# Sheet_1_2024-05-18.net
KiCad netlist of a schematic drawn in Altium Designer
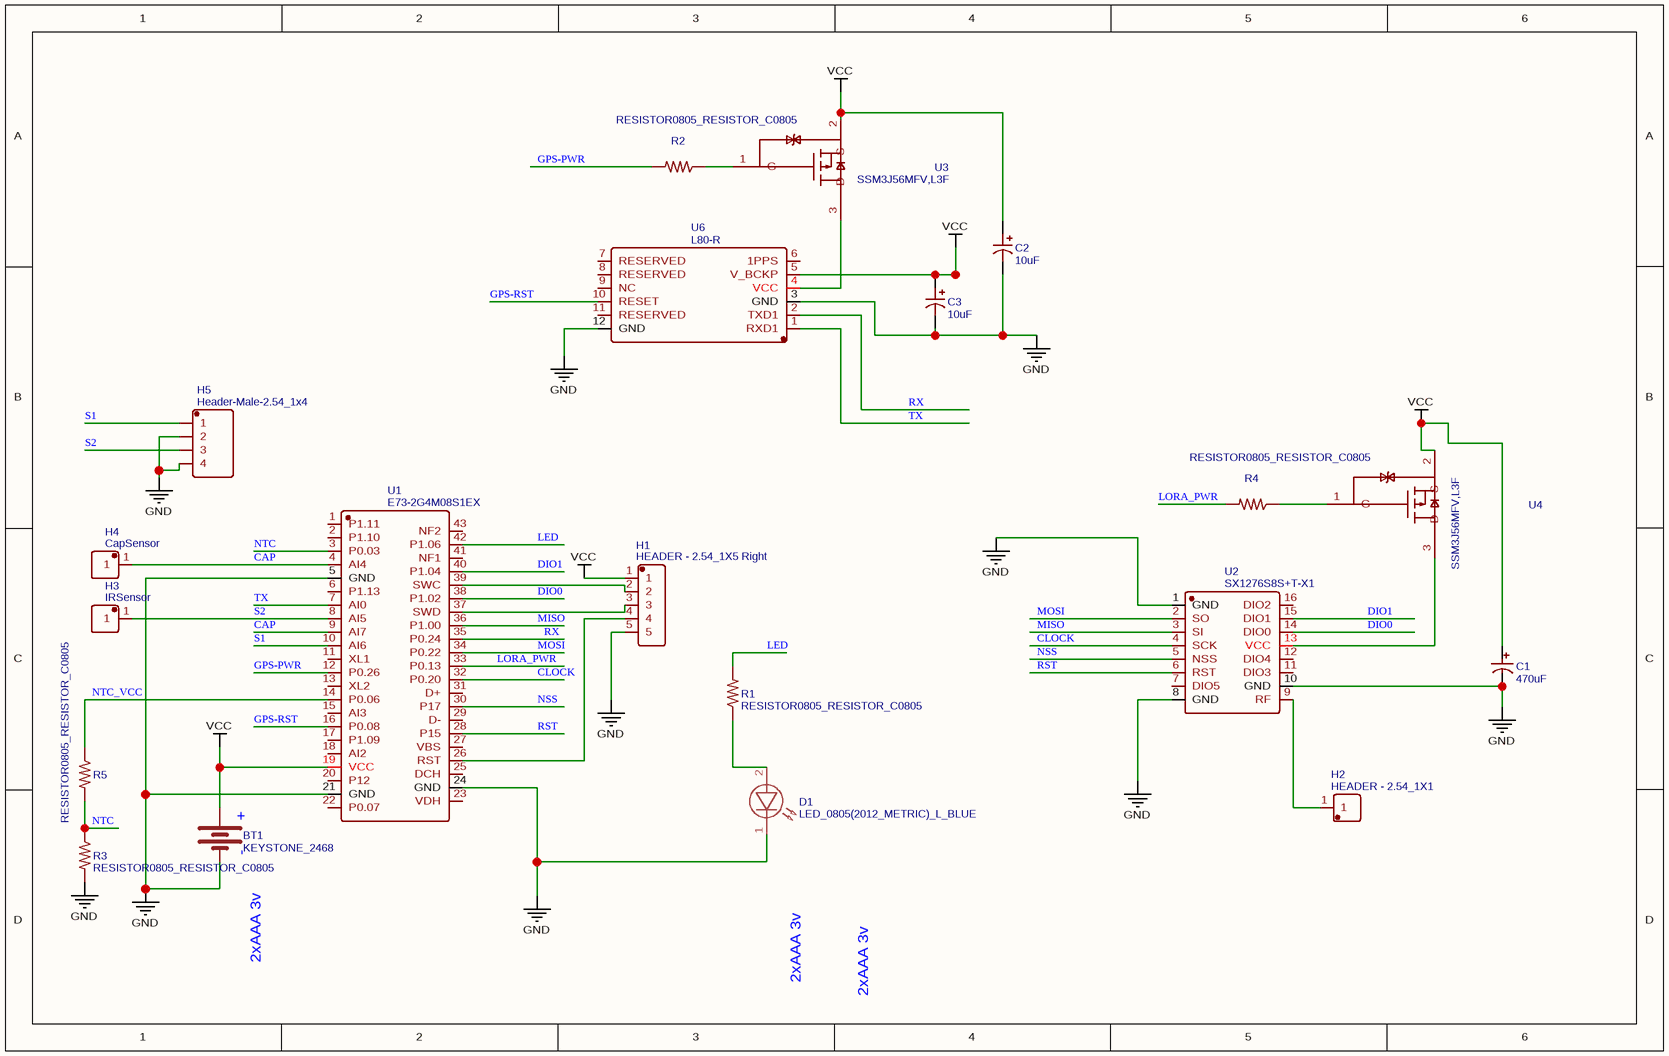
[diagram p0: Sheet_1_2024-05-18.schdoc]

(export (version "E")
  (design (tool "Eeschema 10.0.6"))
  (components
    (comp (ref "BT1")
      (value "KEYSTONE_2468")
      (fields
        (field (name "MANUFACTURER") "Keystone")
        (field (name "MANUFACTURER PART") "2468")
        (field (name "CONTRIBUTOR") "a.karnauh")
      )
      (libsource (lib "altium-import") (part "root_3_KEYSTONE_2468_"))
    )
    (comp (ref "C1")
      (value "470uF")
      (fields
        (field (name "MANUFACTURER") "ValuePro")
        (field (name "MANUFACTURER PART") "470uF 10V白纸 13*25")
        (field (name "CONTRIBUTOR") "baongoc1234abcd")
      )
      (libsource (lib "altium-import") (part "root_3_470uF_"))
    )
    (comp (ref "C2")
      (value "10uF")
      (fields
        (field (name "MANUFACTURER") "CEC(振华新云)")
        (field (name "MANUFACTURER PART") "CA45-B-10V-10UF-K")
        (field (name "CONTRIBUTOR") "lcsc")
      )
      (libsource (lib "altium-import") (part "root_3_10uF_"))
    )
    (comp (ref "C3")
      (value "10uF")
      (fields
        (field (name "MANUFACTURER") "CEC(振华新云)")
        (field (name "MANUFACTURER PART") "CA45-B-10V-10UF-K")
        (field (name "CONTRIBUTOR") "lcsc")
      )
      (libsource (lib "altium-import") (part "root_3_10uF_"))
    )
    (comp (ref "D1")
      (value "LED_0805(2012_METRIC)_L_BLUE")
      (fields (field (name "CONTRIBUTOR") "Ілля Бондаренко"))
      (libsource (lib "altium-import") (part "root_3_LED_0805(2012_METRIC)_L_BLUE_"))
    )
    (comp (ref "H1")
      (value "HEADER - 2.54_1X5 Right")
      (fields (field (name "CONTRIBUTOR") "Jonathan Gainsford"))
      (libsource (lib "altium-import") (part "root_0_HEADER - 2.54_1X5 Right_"))
    )
    (comp (ref "H2")
      (value "HEADER - 2.54_1X1")
      (fields (field (name "CONTRIBUTOR") "ASP-29 Tech"))
      (libsource (lib "altium-import") (part "root_0_HEADER - 2.54_1X1_"))
    )
    (comp (ref "H3")
      (value "IRSensor")
      (fields (field (name "CONTRIBUTOR") "ASP-29 Tech"))
      (libsource (lib "altium-import") (part "root_2_IRSensor_"))
    )
    (comp (ref "H4")
      (value "CapSensor")
      (fields (field (name "CONTRIBUTOR") "ASP-29 Tech"))
      (libsource (lib "altium-import") (part "root_2_CapSensor_"))
    )
    (comp (ref "H5")
      (value "Header-Male-2.54_1x4")
      (fields
        (field (name "MANUFACTURER") "Ckmtw(灿科盟)")
        (field (name "MANUFACTURER PART") "B-2100S04P-A110")
        (field (name "CONTRIBUTOR") "LCSC")
      )
      (libsource (lib "altium-import") (part "root_0_Header-Male-2.54_1x4_"))
    )
    (comp (ref "R1")
      (value "RESISTOR0805_RESISTOR_C0805")
      (fields (field (name "MANUFACTURER") "2.2K"))
      (libsource (lib "altium-import") (part "root_1_RESISTOR0805_RESISTOR_C0805_"))
    )
    (comp (ref "R2")
      (value "RESISTOR0805_RESISTOR_C0805")
      (fields (field (name "MANUFACTURER") "10K"))
      (libsource (lib "altium-import") (part "root_2_RESISTOR0805_RESISTOR_C0805_"))
    )
    (comp (ref "R3")
      (value "RESISTOR0805_RESISTOR_C0805")
      (fields (field (name "MANUFACTURER") "NTC 10K"))
      (libsource (lib "altium-import") (part "root_3_RESISTOR0805_RESISTOR_C0805_"))
    )
    (comp (ref "R4")
      (value "RESISTOR0805_RESISTOR_C0805")
      (fields (field (name "MANUFACTURER") "10K"))
      (libsource (lib "altium-import") (part "root_2_RESISTOR0805_RESISTOR_C0805_"))
    )
    (comp (ref "R5")
      (value "RESISTOR0805_RESISTOR_C0805")
      (fields (field (name "MANUFACTURER") "10K"))
      (libsource (lib "altium-import") (part "root_3_RESISTOR0805_RESISTOR_C0805_"))
    )
    (comp (ref "U1")
      (value "E73-2G4M08S1EX")
      (fields (field (name "MANUFACTURER") "EBYTE(亿佰特)") (field (name "CONTRIBUTOR") "lcsc"))
      (libsource (lib "altium-import") (part "root_0_E73-2G4M08S1EX_"))
    )
    (comp (ref "U2")
      (value "SX1276S8S+T-X1")
      (fields (field (name "MANUFACTURER") "Vollgo(沃进)") (field (name "CONTRIBUTOR") "LCSC"))
      (libsource (lib "altium-import") (part "root_0_SX1276S8S+T-X1_"))
    )
    (comp (ref "U3")
      (value "SSM3J56MFV,L3F")
      (fields (field (name "MANUFACTURER") "TOSHIBA(东芝)") (field (name "CONTRIBUTOR") "lcsc"))
      (libsource (lib "altium-import") (part "root_2_SSM3J56MFV,L3F_"))
    )
    (comp (ref "U4")
      (value "SSM3J56MFV,L3F")
      (fields (field (name "MANUFACTURER") "TOSHIBA(东芝)") (field (name "CONTRIBUTOR") "lcsc"))
      (libsource (lib "altium-import") (part "root_2_SSM3J56MFV,L3F_"))
    )
    (comp (ref "U6")
      (value "L80-R")
      (fields (field (name "MANUFACTURER") "Quectel(移远)") (field (name "CONTRIBUTOR") "LCSC"))
      (libsource (lib "altium-import") (part "root_0_L80-R_"))
    )
  )
  (nets
    (net (code "1") (name "/CAP") (class "Default")
      (node (ref "H4") (pin "1") (pinfunction "1_1") (pintype "passive"))
      (node (ref "U1") (pin "4") (pinfunction "AI4_4") (pintype "passive"))
      (node (ref "U1") (pin "9") (pinfunction "AI7_9") (pintype "passive"))
    )
    (net (code "2") (name "/CLOCK") (class "Default")
      (node (ref "U1") (pin "32") (pinfunction "P0.20_32") (pintype "passive"))
      (node (ref "U2") (pin "4") (pinfunction "SCK_4") (pintype "passive"))
    )
    (net (code "3") (name "/DIO0") (class "Default")
      (node (ref "U1") (pin "38") (pinfunction "P1.02_38") (pintype "passive"))
      (node (ref "U2") (pin "14") (pinfunction "DIO0_14") (pintype "passive"))
    )
    (net (code "4") (name "/DIO1") (class "Default")
      (node (ref "U1") (pin "40") (pinfunction "P1.04_40") (pintype "passive"))
      (node (ref "U2") (pin "15") (pinfunction "DIO1_15") (pintype "passive"))
    )
    (net (code "5") (name "/GPS-PWR") (class "Default")
      (node (ref "R2") (pin "2") (pinfunction "2_2") (pintype "passive"))
      (node (ref "U1") (pin "12") (pinfunction "P0.26_12") (pintype "passive"))
    )
    (net (code "6") (name "/GPS-RST") (class "Default")
      (node (ref "U1") (pin "16") (pinfunction "P0.08_16") (pintype "passive"))
      (node (ref "U6") (pin "10") (pinfunction "RESET_10") (pintype "passive"))
    )
    (net (code "7") (name "/LED") (class "Default")
      (node (ref "R1") (pin "2") (pinfunction "2_2") (pintype "passive"))
      (node (ref "U1") (pin "42") (pinfunction "P1.06_42") (pintype "passive"))
    )
    (net (code "8") (name "/LORA_PWR") (class "Default")
      (node (ref "R4") (pin "2") (pinfunction "2_2") (pintype "passive"))
      (node (ref "U1") (pin "33") (pinfunction "P0.13_33") (pintype "passive"))
    )
    (net (code "9") (name "/MISO") (class "Default")
      (node (ref "U1") (pin "36") (pinfunction "P1.00_36") (pintype "passive"))
      (node (ref "U2") (pin "3") (pinfunction "SI_3") (pintype "passive"))
    )
    (net (code "10") (name "/MOSI") (class "Default")
      (node (ref "U1") (pin "34") (pinfunction "P0.22_34") (pintype "passive"))
      (node (ref "U2") (pin "2") (pinfunction "SO_2") (pintype "passive"))
    )
    (net (code "11") (name "/NSS") (class "Default")
      (node (ref "U1") (pin "30") (pinfunction "P17_30") (pintype "passive"))
      (node (ref "U2") (pin "5") (pinfunction "NSS_5") (pintype "passive"))
    )
    (net (code "12") (name "/NTC") (class "Default")
      (node (ref "R3") (pin "1") (pinfunction "1_1") (pintype "passive"))
      (node (ref "R5") (pin "2") (pinfunction "2_2") (pintype "passive"))
      (node (ref "U1") (pin "3") (pinfunction "P0.03_3") (pintype "passive"))
    )
    (net (code "13") (name "/NTC_VCC") (class "Default")
      (node (ref "R5") (pin "1") (pinfunction "1_1") (pintype "passive"))
      (node (ref "U1") (pin "14") (pinfunction "P0.06_14") (pintype "passive"))
    )
    (net (code "14") (name "/RST") (class "Default")
      (node (ref "U1") (pin "28") (pinfunction "P15_28") (pintype "passive"))
      (node (ref "U2") (pin "6") (pinfunction "RST_6") (pintype "passive"))
    )
    (net (code "15") (name "/RX") (class "Default")
      (node (ref "U1") (pin "35") (pinfunction "P0.24_35") (pintype "passive"))
      (node (ref "U6") (pin "2") (pinfunction "TXD1_2") (pintype "passive"))
    )
    (net (code "16") (name "/S1") (class "Default")
      (node (ref "H5") (pin "1") (pinfunction "1_1") (pintype "passive"))
      (node (ref "U1") (pin "10") (pinfunction "AI6_10") (pintype "passive"))
    )
    (net (code "17") (name "/S2") (class "Default")
      (node (ref "H3") (pin "1") (pinfunction "1_1") (pintype "passive"))
      (node (ref "H5") (pin "3") (pinfunction "3_3") (pintype "passive"))
      (node (ref "U1") (pin "8") (pinfunction "AI5_8") (pintype "passive"))
    )
    (net (code "18") (name "/TX") (class "Default")
      (node (ref "U1") (pin "7") (pinfunction "AI0_7") (pintype "passive"))
      (node (ref "U6") (pin "1") (pinfunction "RXD1_1") (pintype "passive"))
    )
    (net (code "19") (name "GND") (class "Default")
      (node (ref "BT1") (pin "2") (pinfunction "-_2") (pintype "passive"))
      (node (ref "C1") (pin "2") (pinfunction "2_2") (pintype "passive"))
      (node (ref "C2") (pin "2") (pinfunction "2_2") (pintype "passive"))
      (node (ref "C3") (pin "2") (pinfunction "2_2") (pintype "passive"))
      (node (ref "D1") (pin "1") (pinfunction "K_1") (pintype "passive"))
      (node (ref "H1") (pin "5") (pinfunction "5_5") (pintype "passive"))
      (node (ref "H5") (pin "2") (pinfunction "2_2") (pintype "passive"))
      (node (ref "H5") (pin "4") (pinfunction "4_4") (pintype "passive"))
      (node (ref "R3") (pin "2") (pinfunction "2_2") (pintype "passive"))
      (node (ref "U1") (pin "21") (pinfunction "GND_21") (pintype "passive"))
      (node (ref "U1") (pin "24") (pinfunction "GND_24") (pintype "passive"))
      (node (ref "U1") (pin "5") (pinfunction "GND_5") (pintype "passive"))
      (node (ref "U2") (pin "1") (pinfunction "GND_1") (pintype "passive"))
      (node (ref "U2") (pin "10") (pinfunction "GND_10") (pintype "passive"))
      (node (ref "U2") (pin "8") (pinfunction "GND_8") (pintype "passive"))
      (node (ref "U6") (pin "12") (pinfunction "GND_12") (pintype "passive"))
      (node (ref "U6") (pin "3") (pinfunction "GND_3") (pintype "passive"))
    )
    (net (code "20") (name "Net-(D1-A)") (class "Default")
      (node (ref "D1") (pin "2") (pinfunction "A_2") (pintype "passive"))
      (node (ref "R1") (pin "1") (pinfunction "1_1") (pintype "passive"))
    )
    (net (code "21") (name "Net-(U1-RST)") (class "Default")
      (node (ref "H1") (pin "4") (pinfunction "4_4") (pintype "passive"))
      (node (ref "U1") (pin "26") (pinfunction "RST_26") (pintype "passive"))
    )
    (net (code "22") (name "Net-(U1-SWC)") (class "Default")
      (node (ref "H1") (pin "2") (pinfunction "2_2") (pintype "passive"))
      (node (ref "U1") (pin "39") (pinfunction "SWC_39") (pintype "passive"))
    )
    (net (code "23") (name "Net-(U1-SWD)") (class "Default")
      (node (ref "H1") (pin "3") (pinfunction "3_3") (pintype "passive"))
      (node (ref "U1") (pin "37") (pinfunction "SWD_37") (pintype "passive"))
    )
    (net (code "24") (name "Net-(U2-RF)") (class "Default")
      (node (ref "H2") (pin "1") (pinfunction "1_1") (pintype "passive"))
      (node (ref "U2") (pin "9") (pinfunction "RF_9") (pintype "passive"))
    )
    (net (code "25") (name "Net-(U2-VCC)") (class "Default")
      (node (ref "U2") (pin "13") (pinfunction "VCC_13") (pintype "passive"))
      (node (ref "U4") (pin "3") (pinfunction "D_3") (pintype "passive"))
    )
    (net (code "26") (name "Net-(U3-D)") (class "Default")
      (node (ref "U3") (pin "3") (pinfunction "D_3") (pintype "passive"))
      (node (ref "U6") (pin "4") (pinfunction "VCC_4") (pintype "passive"))
    )
    (net (code "27") (name "Net-(U3-G)") (class "Default")
      (node (ref "R2") (pin "1") (pinfunction "1_1") (pintype "passive"))
      (node (ref "U3") (pin "1") (pinfunction "G_1") (pintype "passive"))
    )
    (net (code "28") (name "Net-(U4-G)") (class "Default")
      (node (ref "R4") (pin "1") (pinfunction "1_1") (pintype "passive"))
      (node (ref "U4") (pin "1") (pinfunction "G_1") (pintype "passive"))
    )
    (net (code "29") (name "VCC") (class "Default")
      (node (ref "BT1") (pin "1") (pinfunction "+_1") (pintype "passive"))
      (node (ref "C1") (pin "1") (pinfunction "1_1") (pintype "passive"))
      (node (ref "C2") (pin "1") (pinfunction "1_1") (pintype "passive"))
      (node (ref "C3") (pin "1") (pinfunction "1_1") (pintype "passive"))
      (node (ref "H1") (pin "1") (pinfunction "1_1") (pintype "passive"))
      (node (ref "U1") (pin "19") (pinfunction "VCC_19") (pintype "passive"))
      (node (ref "U3") (pin "2") (pinfunction "S_2") (pintype "passive"))
      (node (ref "U4") (pin "2") (pinfunction "S_2") (pintype "passive"))
      (node (ref "U6") (pin "5") (pinfunction "V_BCKP_5") (pintype "passive"))
    )
    (net (code "30") (name "unconnected-(U1-AI2-Pad18)") (class "Default")
      (node (ref "U1") (pin "18") (pinfunction "AI2_18") (pintype "passive"))
    )
    (net (code "31") (name "unconnected-(U1-AI3-Pad15)") (class "Default")
      (node (ref "U1") (pin "15") (pinfunction "AI3_15") (pintype "passive"))
    )
    (net (code "32") (name "unconnected-(U1-D+-Pad31)") (class "Default")
      (node (ref "U1") (pin "31") (pinfunction "D+_31") (pintype "passive"))
    )
    (net (code "33") (name "unconnected-(U1-D--Pad29)") (class "Default")
      (node (ref "U1") (pin "29") (pinfunction "D-_29") (pintype "passive"))
    )
    (net (code "34") (name "unconnected-(U1-DCH-Pad25)") (class "Default")
      (node (ref "U1") (pin "25") (pinfunction "DCH_25") (pintype "passive"))
    )
    (net (code "35") (name "unconnected-(U1-NF1-Pad41)") (class "Default")
      (node (ref "U1") (pin "41") (pinfunction "NF1_41") (pintype "passive"))
    )
    (net (code "36") (name "unconnected-(U1-NF2-Pad43)") (class "Default")
      (node (ref "U1") (pin "43") (pinfunction "NF2_43") (pintype "passive"))
    )
    (net (code "37") (name "unconnected-(U1-P0.07-Pad22)") (class "Default")
      (node (ref "U1") (pin "22") (pinfunction "P0.07_22") (pintype "passive"))
    )
    (net (code "38") (name "unconnected-(U1-P1.09-Pad17)") (class "Default")
      (node (ref "U1") (pin "17") (pinfunction "P1.09_17") (pintype "passive"))
    )
    (net (code "39") (name "unconnected-(U1-P1.10-Pad2)") (class "Default")
      (node (ref "U1") (pin "2") (pinfunction "P1.10_2") (pintype "passive"))
    )
    (net (code "40") (name "unconnected-(U1-P1.11-Pad1)") (class "Default")
      (node (ref "U1") (pin "1") (pinfunction "P1.11_1") (pintype "passive"))
    )
    (net (code "41") (name "unconnected-(U1-P1.13-Pad6)") (class "Default")
      (node (ref "U1") (pin "6") (pinfunction "P1.13_6") (pintype "passive"))
    )
    (net (code "42") (name "unconnected-(U1-P12-Pad20)") (class "Default")
      (node (ref "U1") (pin "20") (pinfunction "P12_20") (pintype "passive"))
    )
    (net (code "43") (name "unconnected-(U1-VBS-Pad27)") (class "Default")
      (node (ref "U1") (pin "27") (pinfunction "VBS_27") (pintype "passive"))
    )
    (net (code "44") (name "unconnected-(U1-VDH-Pad23)") (class "Default")
      (node (ref "U1") (pin "23") (pinfunction "VDH_23") (pintype "passive"))
    )
    (net (code "45") (name "unconnected-(U1-XL1-Pad11)") (class "Default")
      (node (ref "U1") (pin "11") (pinfunction "XL1_11") (pintype "passive"))
    )
    (net (code "46") (name "unconnected-(U1-XL2-Pad13)") (class "Default")
      (node (ref "U1") (pin "13") (pinfunction "XL2_13") (pintype "passive"))
    )
    (net (code "47") (name "unconnected-(U2-DIO2-Pad16)") (class "Default")
      (node (ref "U2") (pin "16") (pinfunction "DIO2_16") (pintype "passive"))
    )
    (net (code "48") (name "unconnected-(U2-DIO3-Pad11)") (class "Default")
      (node (ref "U2") (pin "11") (pinfunction "DIO3_11") (pintype "passive"))
    )
    (net (code "49") (name "unconnected-(U2-DIO4-Pad12)") (class "Default")
      (node (ref "U2") (pin "12") (pinfunction "DIO4_12") (pintype "passive"))
    )
    (net (code "50") (name "unconnected-(U2-DIO5-Pad7)") (class "Default")
      (node (ref "U2") (pin "7") (pinfunction "DIO5_7") (pintype "passive"))
    )
    (net (code "51") (name "unconnected-(U6-1PPS-Pad6)") (class "Default")
      (node (ref "U6") (pin "6") (pinfunction "1PPS_6") (pintype "passive"))
    )
    (net (code "52") (name "unconnected-(U6-NC-Pad9)") (class "Default")
      (node (ref "U6") (pin "9") (pinfunction "NC_9") (pintype "passive"))
    )
    (net (code "53") (name "unconnected-(U6-RESERVED-Pad7)") (class "Default")
      (node (ref "U6") (pin "7") (pinfunction "RESERVED_7") (pintype "passive"))
    )
    (net (code "54") (name "unconnected-(U6-RESERVED-Pad8)") (class "Default")
      (node (ref "U6") (pin "8") (pinfunction "RESERVED_8") (pintype "passive"))
    )
    (net (code "55") (name "unconnected-(U6-RESERVED-Pad11)") (class "Default")
      (node (ref "U6") (pin "11") (pinfunction "RESERVED_11") (pintype "passive"))
    )
  )
)
